# NFC.net
KiCad netlist of a schematic drawn in Altium Designer
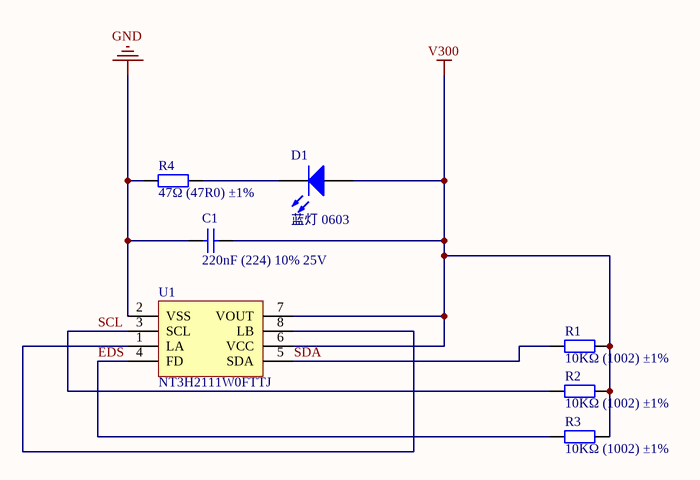
[diagram p0: NFC名片.SchDoc]

(export (version "E")
  (design (tool "Eeschema 10.0.6"))
  (components
    (comp (ref "C1")
      (value "220nF (224) 10% 25V")
      (footprint "0603_C")
      (description "贴片电容")
      (libsource (lib "Miscellaneous Devices LC") (part "0603 220nF (224) 10% 25V"))
    )
    (comp (ref "D1")
      (value "蓝灯 0603")
      (footprint "0603_LED_S1")
      (description "发光二极管")
      (libsource (lib "Miscellaneous Devices LC") (part "0603 蓝灯"))
    )
    (comp (ref "R1")
      (value "10KΩ (1002) ±1%")
      (footprint "0603_R")
      (description "贴片电阻")
      (libsource (lib "Miscellaneous Devices LC") (part "0603 10KΩ (1002) 1%"))
    )
    (comp (ref "R2")
      (value "10KΩ (1002) ±1%")
      (footprint "0603_R")
      (description "贴片电阻")
      (libsource (lib "Miscellaneous Devices LC") (part "0603 10KΩ (1002) 1%"))
    )
    (comp (ref "R3")
      (value "10KΩ (1002) ±1%")
      (footprint "0603_R")
      (description "贴片电阻")
      (libsource (lib "Miscellaneous Devices LC") (part "0603 10KΩ (1002) 1%"))
    )
    (comp (ref "R4")
      (value "47Ω (47R0) ±1%")
      (footprint "0603_R")
      (description "贴片电阻")
      (libsource (lib "Miscellaneous Devices LC") (part "0603 47Ω (47R0) 1%"))
    )
    (comp (ref "U1")
      (value "NT3H2111W0FTTJ")
      (footprint "TSSOP-8")
      (libsource (lib "小七的原理图库") (part "IR2101S"))
    )
  )
  (nets
    (net (code "1") (name "/EDS") (class "Default")
      (node (ref "R3") (pin "1") (pinfunction "1_1") (pintype "passive"))
      (node (ref "U1") (pin "4") (pinfunction "FD_4") (pintype "passive"))
    )
    (net (code "2") (name "/SCL") (class "Default")
      (node (ref "R2") (pin "1") (pinfunction "1_1") (pintype "passive"))
      (node (ref "U1") (pin "3") (pinfunction "SCL_3") (pintype "passive"))
    )
    (net (code "3") (name "/SDA") (class "Default")
      (node (ref "R1") (pin "1") (pinfunction "1_1") (pintype "passive"))
      (node (ref "U1") (pin "5") (pinfunction "SDA_5") (pintype "passive"))
    )
    (net (code "4") (name "GND") (class "Default")
      (node (ref "C1") (pin "1") (pinfunction "1_1") (pintype "passive"))
      (node (ref "R4") (pin "1") (pinfunction "1_1") (pintype "passive"))
      (node (ref "U1") (pin "2") (pinfunction "VSS_2") (pintype "passive"))
    )
    (net (code "5") (name "Net-(D1-PadK)") (class "Default")
      (node (ref "D1") (pin "K") (pinfunction "K_K") (pintype "passive"))
      (node (ref "R4") (pin "2") (pinfunction "2_2") (pintype "passive"))
    )
    (net (code "6") (name "Net-(U1-LA)") (class "Default")
      (node (ref "U1") (pin "1") (pinfunction "LA_1") (pintype "passive"))
      (node (ref "U1") (pin "8") (pinfunction "LB_8") (pintype "passive"))
    )
    (net (code "7") (name "V300") (class "Default")
      (node (ref "C1") (pin "2") (pinfunction "2_2") (pintype "passive"))
      (node (ref "D1") (pin "A") (pinfunction "A_A") (pintype "passive"))
      (node (ref "R1") (pin "2") (pinfunction "2_2") (pintype "passive"))
      (node (ref "R2") (pin "2") (pinfunction "2_2") (pintype "passive"))
      (node (ref "R3") (pin "2") (pinfunction "2_2") (pintype "passive"))
      (node (ref "U1") (pin "6") (pinfunction "VCC_6") (pintype "passive"))
      (node (ref "U1") (pin "7") (pinfunction "VOUT_7") (pintype "passive"))
    )
  )
)
